# H-00488_-_Connectors_Upstream.net
KiCad netlist of a schematic drawn in Altium Designer
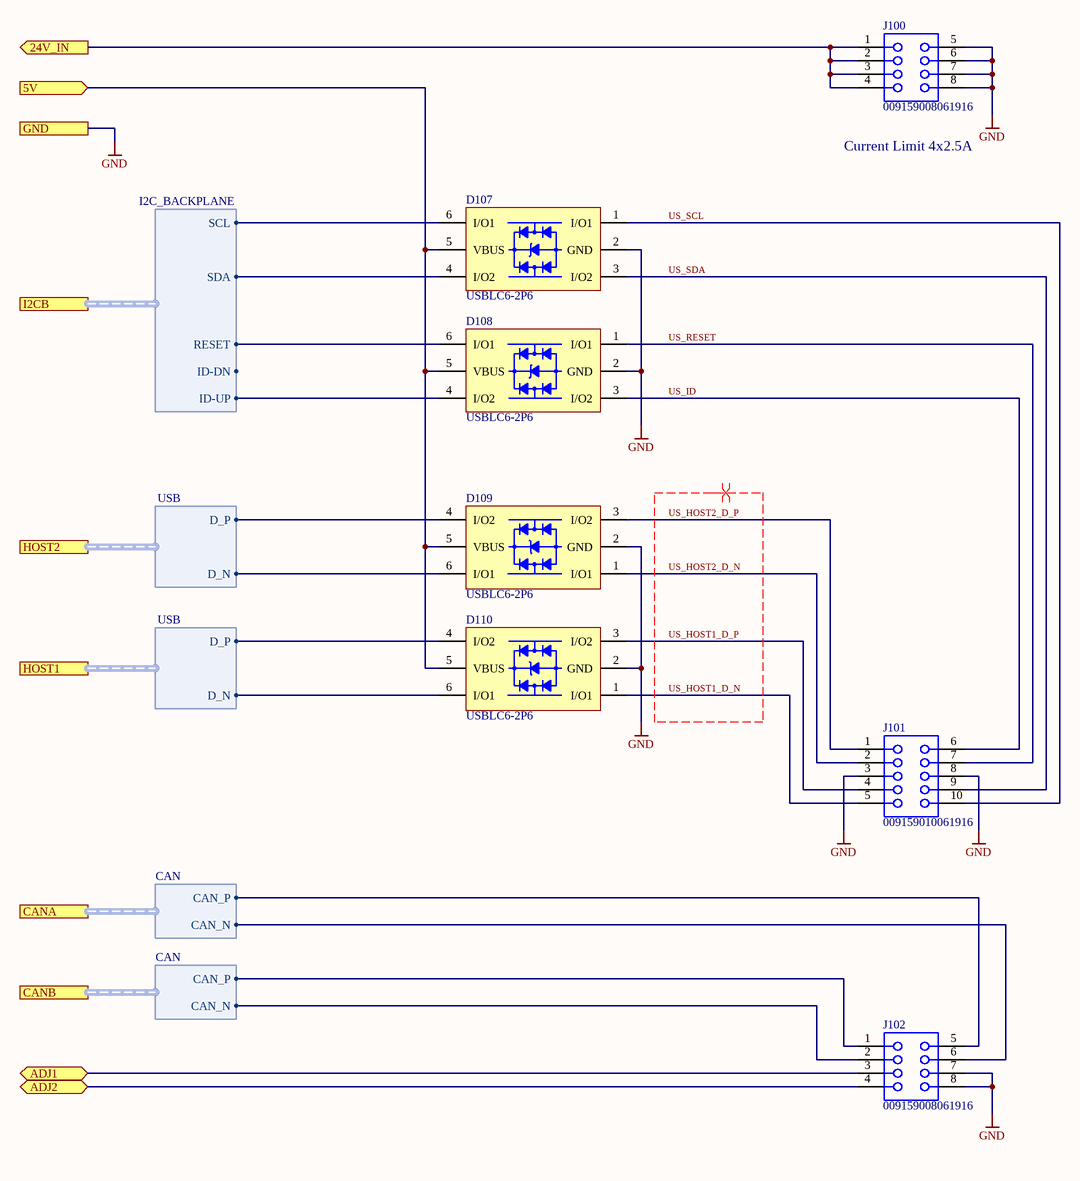
[diagram p0: H-00488 - Connectors Upstream.SchDoc]

(export (version "E")
  (design (tool "Eeschema 10.0.6"))
  (components
    (comp (ref "D107")
      (value "USBLC6-2P6")
      (footprint "DIOSOFL6P50_160X160X95L29X26")
      (description "TVS DIODE 5.25VWM 17VC SOT666")
      (libsource (lib "Hiber") (part "ST_USBLC6-2"))
    )
    (comp (ref "D108")
      (value "USBLC6-2P6")
      (footprint "DIOSOFL6P50_160X160X95L29X26")
      (description "TVS DIODE 5.25VWM 17VC SOT666")
      (libsource (lib "Hiber") (part "ST_USBLC6-2"))
    )
    (comp (ref "D109")
      (value "USBLC6-2P6")
      (footprint "DIOSOFL6P50_160X160X95L29X26")
      (description "TVS DIODE 5.25VWM 17VC SOT666")
      (libsource (lib "") (part "ST_USBLC6-2_1"))
    )
    (comp (ref "D110")
      (value "USBLC6-2P6")
      (footprint "DIOSOFL6P50_160X160X95L29X26")
      (description "TVS DIODE 5.25VWM 17VC SOT666")
      (libsource (lib "") (part "ST_USBLC6-2_1"))
    )
    (comp (ref "J100")
      (value "009159008061916")
      (footprint "AVX_00-9159-008")
      (description "CONN SSL BRIDGE 8POS 2MM")
      (libsource (lib "Hiber") (part "HEADER-FEMALE-02X04-N"))
    )
    (comp (ref "J101")
      (value "009159010061916")
      (footprint "AVX_00-9159-010")
      (description "AVX INTERCONNECT - 009159010061916 - CARD EDGE CONN, DUAL SIDE, 10POS, SMD")
      (libsource (lib "Hiber") (part "HEADER-FEMALE-02X05-N"))
    )
    (comp (ref "J102")
      (value "009159008061916")
      (footprint "AVX_00-9159-008")
      (description "CONN SSL BRIDGE 8POS 2MM")
      (libsource (lib "Hiber") (part "HEADER-FEMALE-02X04-N"))
    )
  )
  (nets
    (net (code "4") (name "/5V") (class "Default")
      (node (ref "D107") (pin "5") (pinfunction "VBUS_5") (pintype "passive"))
      (node (ref "D108") (pin "5") (pinfunction "VBUS_5") (pintype "passive"))
      (node (ref "D109") (pin "5") (pinfunction "VBUS_5") (pintype "passive"))
      (node (ref "D110") (pin "5") (pinfunction "VBUS_5") (pintype "passive"))
    )
    (net (code "5") (name "/24V_IN") (class "Default")
      (node (ref "J100") (pin "1") (pinfunction "1_1") (pintype "passive"))
      (node (ref "J100") (pin "2") (pinfunction "2_2") (pintype "passive"))
      (node (ref "J100") (pin "3") (pinfunction "3_3") (pintype "passive"))
      (node (ref "J100") (pin "4") (pinfunction "4_4") (pintype "passive"))
    )
    (net (code "6") (name "/ADJ1") (class "Default")
      (node (ref "J102") (pin "3") (pinfunction "3_3") (pintype "passive"))
    )
    (net (code "7") (name "/ADJ2") (class "Default")
      (node (ref "J102") (pin "4") (pinfunction "4_4") (pintype "passive"))
    )
    (net (code "8") (name "/ID-UP") (class "Default")
      (node (ref "D108") (pin "4") (pinfunction "I/O2_4") (pintype "passive"))
    )
    (net (code "9") (name "/RESET") (class "Default")
      (node (ref "D108") (pin "6") (pinfunction "I/O1_6") (pintype "passive"))
    )
    (net (code "10") (name "/SCL") (class "Default")
      (node (ref "D107") (pin "6") (pinfunction "I/O1_6") (pintype "passive"))
    )
    (net (code "11") (name "/SDA") (class "Default")
      (node (ref "D107") (pin "4") (pinfunction "I/O2_4") (pintype "passive"))
    )
    (net (code "12") (name "/US_HOST1_D_N") (class "Default")
      (node (ref "D110") (pin "1") (pinfunction "I/O1_1") (pintype "passive"))
      (node (ref "J101") (pin "5") (pinfunction "5_5") (pintype "passive"))
    )
    (net (code "13") (name "/US_HOST1_D_P") (class "Default")
      (node (ref "D110") (pin "3") (pinfunction "I/O2_3") (pintype "passive"))
      (node (ref "J101") (pin "4") (pinfunction "4_4") (pintype "passive"))
    )
    (net (code "14") (name "/US_HOST2_D_N") (class "Default")
      (node (ref "D109") (pin "1") (pinfunction "I/O1_1") (pintype "passive"))
      (node (ref "J101") (pin "2") (pinfunction "2_2") (pintype "passive"))
    )
    (net (code "15") (name "/US_HOST2_D_P") (class "Default")
      (node (ref "D109") (pin "3") (pinfunction "I/O2_3") (pintype "passive"))
      (node (ref "J101") (pin "1") (pinfunction "1_1") (pintype "passive"))
    )
    (net (code "16") (name "/US_ID") (class "Default")
      (node (ref "D108") (pin "3") (pinfunction "I/O2_3") (pintype "passive"))
      (node (ref "J101") (pin "6") (pinfunction "6_6") (pintype "passive"))
    )
    (net (code "17") (name "/US_RESET") (class "Default")
      (node (ref "D108") (pin "1") (pinfunction "I/O1_1") (pintype "passive"))
      (node (ref "J101") (pin "7") (pinfunction "7_7") (pintype "passive"))
    )
    (net (code "18") (name "/US_SCL") (class "Default")
      (node (ref "D107") (pin "1") (pinfunction "I/O1_1") (pintype "passive"))
      (node (ref "J101") (pin "10") (pinfunction "10_10") (pintype "passive"))
    )
    (net (code "19") (name "/US_SDA") (class "Default")
      (node (ref "D107") (pin "3") (pinfunction "I/O2_3") (pintype "passive"))
      (node (ref "J101") (pin "9") (pinfunction "9_9") (pintype "passive"))
    )
    (net (code "23") (name "GND") (class "Default")
      (node (ref "D107") (pin "2") (pinfunction "GND_2") (pintype "passive"))
      (node (ref "D108") (pin "2") (pinfunction "GND_2") (pintype "passive"))
      (node (ref "D109") (pin "2") (pinfunction "GND_2") (pintype "passive"))
      (node (ref "D110") (pin "2") (pinfunction "GND_2") (pintype "passive"))
      (node (ref "J100") (pin "5") (pinfunction "5_5") (pintype "passive"))
      (node (ref "J100") (pin "6") (pinfunction "6_6") (pintype "passive"))
      (node (ref "J100") (pin "7") (pinfunction "7_7") (pintype "passive"))
      (node (ref "J100") (pin "8") (pinfunction "8_8") (pintype "passive"))
      (node (ref "J101") (pin "3") (pinfunction "3_3") (pintype "passive"))
      (node (ref "J101") (pin "8") (pinfunction "8_8") (pintype "passive"))
      (node (ref "J102") (pin "7") (pinfunction "7_7") (pintype "passive"))
      (node (ref "J102") (pin "8") (pinfunction "8_8") (pintype "passive"))
    )
    (net (code "24") (name "unconnected-(D109-I{slash}O1-Pad6)") (class "Default")
      (node (ref "D109") (pin "6") (pinfunction "I/O1_6") (pintype "passive"))
    )
    (net (code "25") (name "unconnected-(D109-I{slash}O2-Pad4)") (class "Default")
      (node (ref "D109") (pin "4") (pinfunction "I/O2_4") (pintype "passive"))
    )
    (net (code "26") (name "unconnected-(D110-I{slash}O1-Pad6)") (class "Default")
      (node (ref "D110") (pin "6") (pinfunction "I/O1_6") (pintype "passive"))
    )
    (net (code "27") (name "unconnected-(D110-I{slash}O2-Pad4)") (class "Default")
      (node (ref "D110") (pin "4") (pinfunction "I/O2_4") (pintype "passive"))
    )
    (net (code "28") (name "unconnected-(J102-Pad1)") (class "Default")
      (node (ref "J102") (pin "1") (pinfunction "1_1") (pintype "passive"))
    )
    (net (code "29") (name "unconnected-(J102-Pad2)") (class "Default")
      (node (ref "J102") (pin "2") (pinfunction "2_2") (pintype "passive"))
    )
    (net (code "30") (name "unconnected-(J102-Pad5)") (class "Default")
      (node (ref "J102") (pin "5") (pinfunction "5_5") (pintype "passive"))
    )
    (net (code "31") (name "unconnected-(J102-Pad6)") (class "Default")
      (node (ref "J102") (pin "6") (pinfunction "6_6") (pintype "passive"))
    )
  )
)
